# Analog-Mux-Breakout-v11.net
KiCad netlist of a schematic drawn in EAGLE
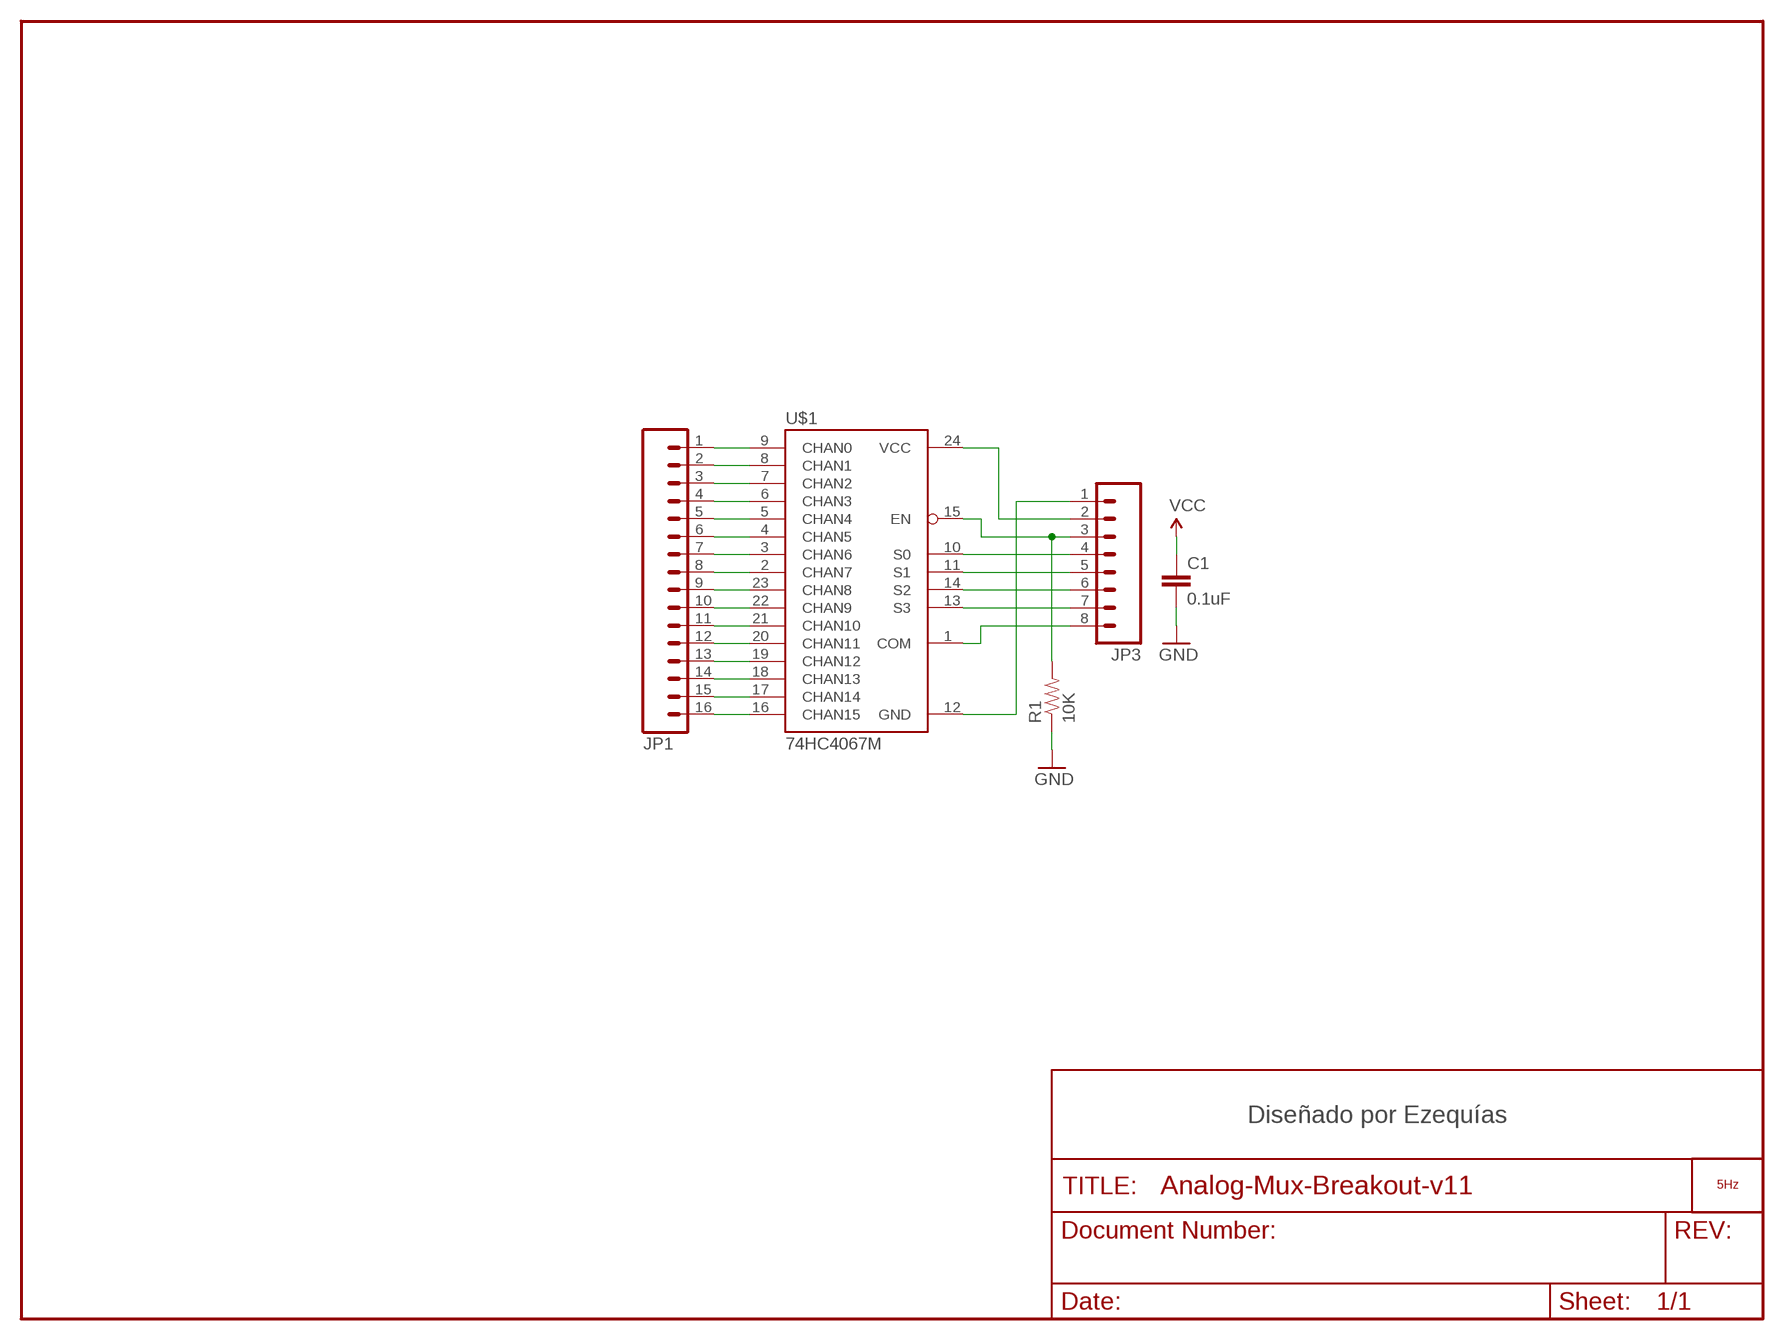
[diagram p0: schematic, sheet 1]

(export (version "E")
  (design (tool "Eeschema 10.0.6"))
  (components
    (comp (ref "C1")
      (value "0.1uF")
      (footprint "eagle-import:C0402")
      (libsource (lib "eagle-import") (part "CAP0402"))
    )
    (comp (ref "JP1")
      (value "M16PTH")
      (footprint "eagle-import:1X16")
      (libsource (lib "eagle-import") (part "M16PTH"))
    )
    (comp (ref "JP3")
      (value "M08")
      (footprint "eagle-import:1X08")
      (libsource (lib "eagle-import") (part "M08"))
    )
    (comp (ref "LOGO1")
      (value "LOGO_5HZ_H_10MM")
      (footprint "eagle-import:5HZ_LOGO_H_10MM")
      (libsource (lib "eagle-import") (part "LOGO_5HZ_H_10MM"))
    )
    (comp (ref "R1")
      (value "10K")
      (footprint "eagle-import:C0402")
      (libsource (lib "eagle-import") (part "RESISTOR0402"))
    )
    (comp (ref "U$1")
      (value "74HC4067M")
      (footprint "eagle-import:SOIC_28")
      (libsource (lib "eagle-import") (part "74HC4067M"))
    )
  )
  (nets
    (net (code "1") (name "GND") (class "Default")
      (node (ref "C1") (pin "2") (pinfunction "2_2") (pintype "passive"))
      (node (ref "JP3") (pin "1") (pinfunction "1_1") (pintype "passive"))
      (node (ref "R1") (pin "1") (pinfunction "1_1") (pintype "passive"))
      (node (ref "U$1") (pin "12") (pinfunction "GND_12") (pintype "bidirectional"))
    )
    (net (code "2") (name "Net-(U$1-CHAN0)") (class "Default")
      (node (ref "JP1") (pin "1") (pinfunction "1_1") (pintype "passive"))
      (node (ref "U$1") (pin "9") (pinfunction "CHAN0_9") (pintype "bidirectional"))
    )
    (net (code "3") (name "Net-(U$1-CHAN1)") (class "Default")
      (node (ref "JP1") (pin "2") (pinfunction "2_2") (pintype "passive"))
      (node (ref "U$1") (pin "8") (pinfunction "CHAN1_8") (pintype "bidirectional"))
    )
    (net (code "4") (name "Net-(U$1-CHAN2)") (class "Default")
      (node (ref "JP1") (pin "3") (pinfunction "3_3") (pintype "passive"))
      (node (ref "U$1") (pin "7") (pinfunction "CHAN2_7") (pintype "bidirectional"))
    )
    (net (code "5") (name "Net-(U$1-CHAN3)") (class "Default")
      (node (ref "JP1") (pin "4") (pinfunction "4_4") (pintype "passive"))
      (node (ref "U$1") (pin "6") (pinfunction "CHAN3_6") (pintype "bidirectional"))
    )
    (net (code "6") (name "Net-(U$1-CHAN4)") (class "Default")
      (node (ref "JP1") (pin "5") (pinfunction "5_5") (pintype "passive"))
      (node (ref "U$1") (pin "5") (pinfunction "CHAN4_5") (pintype "bidirectional"))
    )
    (net (code "7") (name "Net-(U$1-CHAN5)") (class "Default")
      (node (ref "JP1") (pin "6") (pinfunction "6_6") (pintype "passive"))
      (node (ref "U$1") (pin "4") (pinfunction "CHAN5_4") (pintype "bidirectional"))
    )
    (net (code "8") (name "Net-(U$1-CHAN6)") (class "Default")
      (node (ref "JP1") (pin "7") (pinfunction "7_7") (pintype "passive"))
      (node (ref "U$1") (pin "3") (pinfunction "CHAN6_3") (pintype "bidirectional"))
    )
    (net (code "9") (name "Net-(U$1-CHAN7)") (class "Default")
      (node (ref "JP1") (pin "8") (pinfunction "8_8") (pintype "passive"))
      (node (ref "U$1") (pin "2") (pinfunction "CHAN7_2") (pintype "bidirectional"))
    )
    (net (code "10") (name "Net-(U$1-CHAN8)") (class "Default")
      (node (ref "JP1") (pin "9") (pinfunction "9_9") (pintype "passive"))
      (node (ref "U$1") (pin "23") (pinfunction "CHAN8_23") (pintype "bidirectional"))
    )
    (net (code "11") (name "Net-(U$1-CHAN9)") (class "Default")
      (node (ref "JP1") (pin "10") (pinfunction "10_10") (pintype "passive"))
      (node (ref "U$1") (pin "22") (pinfunction "CHAN9_22") (pintype "bidirectional"))
    )
    (net (code "12") (name "Net-(U$1-CHAN10)") (class "Default")
      (node (ref "JP1") (pin "11") (pinfunction "11_11") (pintype "passive"))
      (node (ref "U$1") (pin "21") (pinfunction "CHAN10_21") (pintype "bidirectional"))
    )
    (net (code "13") (name "Net-(U$1-CHAN11)") (class "Default")
      (node (ref "JP1") (pin "12") (pinfunction "12_12") (pintype "passive"))
      (node (ref "U$1") (pin "20") (pinfunction "CHAN11_20") (pintype "bidirectional"))
    )
    (net (code "14") (name "Net-(U$1-CHAN12)") (class "Default")
      (node (ref "JP1") (pin "13") (pinfunction "13_13") (pintype "passive"))
      (node (ref "U$1") (pin "19") (pinfunction "CHAN12_19") (pintype "bidirectional"))
    )
    (net (code "15") (name "Net-(U$1-CHAN13)") (class "Default")
      (node (ref "JP1") (pin "14") (pinfunction "14_14") (pintype "passive"))
      (node (ref "U$1") (pin "18") (pinfunction "CHAN13_18") (pintype "bidirectional"))
    )
    (net (code "16") (name "Net-(U$1-CHAN14)") (class "Default")
      (node (ref "JP1") (pin "15") (pinfunction "15_15") (pintype "passive"))
      (node (ref "U$1") (pin "17") (pinfunction "CHAN14_17") (pintype "bidirectional"))
    )
    (net (code "17") (name "Net-(U$1-CHAN15)") (class "Default")
      (node (ref "JP1") (pin "16") (pinfunction "16_16") (pintype "passive"))
      (node (ref "U$1") (pin "16") (pinfunction "CHAN15_16") (pintype "bidirectional"))
    )
    (net (code "18") (name "Net-(U$1-COM)") (class "Default")
      (node (ref "JP3") (pin "8") (pinfunction "8_8") (pintype "passive"))
      (node (ref "U$1") (pin "1") (pinfunction "COM_1") (pintype "bidirectional"))
    )
    (net (code "19") (name "Net-(U$1-EN)") (class "Default")
      (node (ref "JP3") (pin "3") (pinfunction "3_3") (pintype "passive"))
      (node (ref "R1") (pin "2") (pinfunction "2_2") (pintype "passive"))
      (node (ref "U$1") (pin "15") (pinfunction "EN_15") (pintype "input"))
    )
    (net (code "20") (name "Net-(U$1-S0)") (class "Default")
      (node (ref "JP3") (pin "4") (pinfunction "4_4") (pintype "passive"))
      (node (ref "U$1") (pin "10") (pinfunction "S0_10") (pintype "input"))
    )
    (net (code "21") (name "Net-(U$1-S1)") (class "Default")
      (node (ref "JP3") (pin "5") (pinfunction "5_5") (pintype "passive"))
      (node (ref "U$1") (pin "11") (pinfunction "S1_11") (pintype "input"))
    )
    (net (code "22") (name "Net-(U$1-S2)") (class "Default")
      (node (ref "JP3") (pin "6") (pinfunction "6_6") (pintype "passive"))
      (node (ref "U$1") (pin "14") (pinfunction "S2_14") (pintype "input"))
    )
    (net (code "23") (name "Net-(U$1-S3)") (class "Default")
      (node (ref "JP3") (pin "7") (pinfunction "7_7") (pintype "passive"))
      (node (ref "U$1") (pin "13") (pinfunction "S3_13") (pintype "input"))
    )
    (net (code "24") (name "VCC") (class "Default")
      (node (ref "C1") (pin "1") (pinfunction "1_1") (pintype "passive"))
      (node (ref "JP3") (pin "2") (pinfunction "2_2") (pintype "passive"))
      (node (ref "U$1") (pin "24") (pinfunction "VCC_24") (pintype "bidirectional"))
    )
  )
)
